# YA-S-Power-Supplies-V1_0.net
KiCad netlist of a schematic drawn in Altium Designer
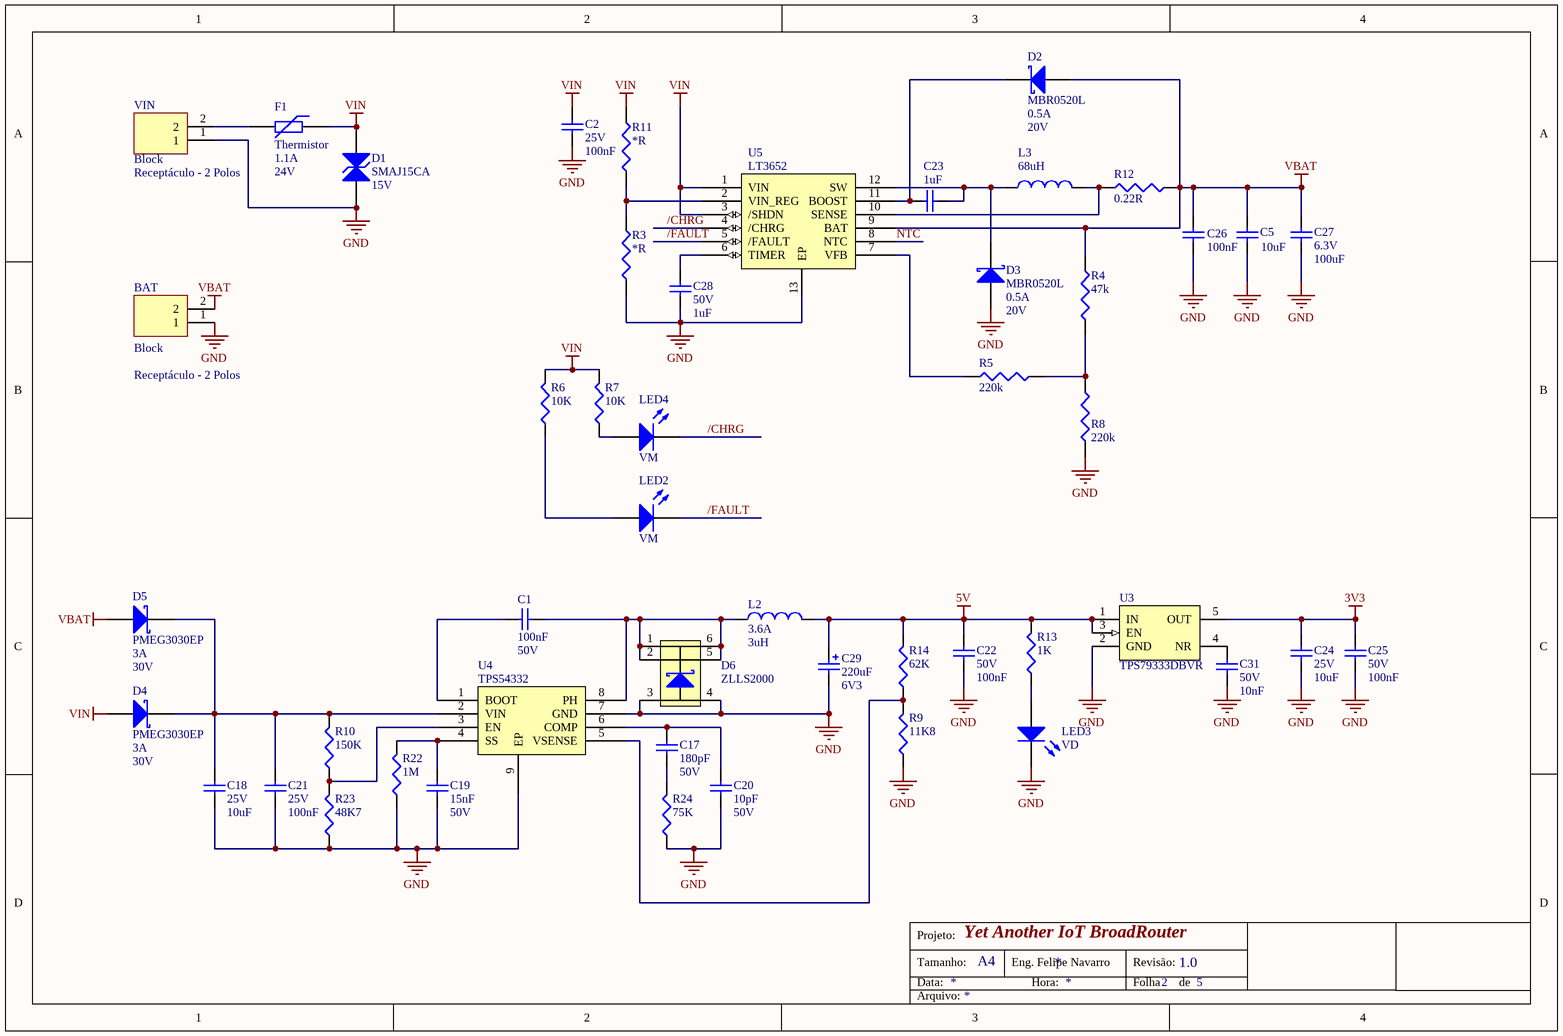
[diagram p0: YA-S-Power-Supplies-V1.0.SchDoc]

(export (version "E")
  (design (tool "Eeschema 10.0.6"))
  (components
    (comp (ref "BAT")
      (value "Block")
      (footprint "CONN SHRD.BL2 RCPT/ V")
      (description "Conector Shrouded Block")
      (fields (field (name "ALTIUM_VALUE") "Receptáculo - 2 Polos"))
      (libsource (lib "NavarroCON") (part "SHRD Block 2P RCPT-V P5.08mm"))
    )
    (comp (ref "C1")
      (value "100nF")
      (footprint "CC0603")
      (description "Capacitor (Semiconductor SIM Model)")
      (fields (field (name "TENSÃO") "50V") (field (name "Comment") "Capacitor Cerâmico"))
      (libsource (lib "NavarroCAP") (part "Cap 100nF 50V 0603 X7R"))
    )
    (comp (ref "C2")
      (value "100nF")
      (footprint "CC0603")
      (description "Capacitor (Semiconductor SIM Model)")
      (fields (field (name "TENSÃO") "25V") (field (name "Comment") "Capacitor Cerâmico"))
      (libsource (lib "NavarroCAP") (part "Cap 100nF 25V 0603 X7R"))
    )
    (comp (ref "C5")
      (value "10uF")
      (footprint "CC0805")
      (description "Capacitor (Semiconductor SIM Model)")
      (fields (field (name "Comment") "Capacitor Cerâmico"))
      (libsource (lib "NavarroCAP") (part "Cap 10uF 50V 1206 X5R"))
    )
    (comp (ref "C17")
      (value "180pF")
      (footprint "CC0603")
      (description "Capacitor (Semiconductor SIM Model)")
      (fields (field (name "TENSÃO") "50V") (field (name "Comment") "Capacitor Cerâmico"))
      (libsource (lib "NavarroCAP") (part "Cap 180pF 50V 0603 NP0"))
    )
    (comp (ref "C18")
      (value "10uF")
      (footprint "CC0805")
      (description "Capacitor (Semiconductor SIM Model)")
      (fields (field (name "TENSÃO") "25V") (field (name "Comment") "Capacitor Cerâmico"))
      (libsource (lib "NavarroCAP") (part "Cap 10uF 25V 0805 X5R"))
    )
    (comp (ref "C19")
      (value "15nF")
      (footprint "CC0603")
      (description "Capacitor (Semiconductor SIM Model)")
      (fields (field (name "TENSÃO") "50V") (field (name "Comment") "Capacitor Cerâmico"))
      (libsource (lib "NavarroCAP") (part "Cap 15nF 50V 0603 X7R"))
    )
    (comp (ref "C20")
      (value "10pF")
      (footprint "CC0603")
      (description "Capacitor (Semiconductor SIM Model)")
      (fields (field (name "TENSÃO") "50V") (field (name "Comment") "Capacitor Cerâmico"))
      (libsource (lib "NavarroCAP") (part "Cap 10pF 50V 0603 NP0 5%"))
    )
    (comp (ref "C21")
      (value "100nF")
      (footprint "CC0603")
      (description "Capacitor (Semiconductor SIM Model)")
      (fields (field (name "TENSÃO") "25V") (field (name "Comment") "Capacitor Cerâmico"))
      (libsource (lib "NavarroCAP") (part "Cap 100nF 25V 0603 X7R"))
    )
    (comp (ref "C22")
      (value "100nF")
      (footprint "CC0603")
      (description "Capacitor (Semiconductor SIM Model)")
      (fields (field (name "TENSÃO") "50V") (field (name "Comment") "Capacitor Cerâmico"))
      (libsource (lib "NavarroCAP") (part "Cap 100nF 50V 0603 X7R"))
    )
    (comp (ref "C23")
      (value "1uF")
      (footprint "CC0603")
      (description "Capacitor (Semiconductor SIM Model)")
      (fields (field (name "Comment") "Capacitor Cerâmico"))
      (libsource (lib "NavarroCAP") (part "Cap 1uF 50V 0603 X5R"))
    )
    (comp (ref "C24")
      (value "10uF")
      (footprint "CC0805")
      (description "Capacitor (Semiconductor SIM Model)")
      (fields (field (name "TENSÃO") "25V") (field (name "Comment") "Capacitor Cerâmico"))
      (libsource (lib "NavarroCAP") (part "Cap 10uF 25V 0805 X5R"))
    )
    (comp (ref "C25")
      (value "100nF")
      (footprint "CC0603")
      (description "Capacitor (Semiconductor SIM Model)")
      (fields (field (name "TENSÃO") "50V") (field (name "Comment") "Capacitor Cerâmico"))
      (libsource (lib "NavarroCAP") (part "Cap 100nF 50V 0603 X7R"))
    )
    (comp (ref "C26")
      (value "100nF")
      (footprint "CC0603")
      (description "Capacitor (Semiconductor SIM Model)")
      (fields (field (name "Comment") "Capacitor Cerâmico"))
      (libsource (lib "NavarroCAP") (part "Cap 100nF 25V 0603 X7R"))
    )
    (comp (ref "C27")
      (value "100uF")
      (footprint "CC1206")
      (description "Capacitor (Semiconductor SIM Model)")
      (fields (field (name "TENSÃO") "6.3V") (field (name "Comment") "Capacitor Cerâmico"))
      (libsource (lib "NavarroCAP") (part "Cap 100uF 6.3V 1206 X5R"))
    )
    (comp (ref "C28")
      (value "1uF")
      (footprint "CC0603")
      (description "Capacitor (Semiconductor SIM Model)")
      (fields (field (name "TENSÃO") "50V") (field (name "Comment") "Capacitor Cerâmico"))
      (libsource (lib "NavarroCAP") (part "Cap 1uF 50V 0603 X5R"))
    )
    (comp (ref "C29")
      (value "220uF")
      (footprint "CPOL2917")
      (description "Polarized Capacitor")
      (fields (field (name "TENSÃO") "6V3") (field (name "Comment") "Capacitor Tântalo"))
      (libsource (lib "NavarroCAP") (part "PCap 220uF 6V3 2917 LOESR"))
    )
    (comp (ref "C31")
      (value "10nF")
      (footprint "CC0603")
      (description "Capacitor (Semiconductor SIM Model)")
      (fields (field (name "TENSÃO") "50V") (field (name "Comment") "Capacitor Cerâmico"))
      (libsource (lib "NavarroCAP") (part "Cap 10nF 50V 0603 X7R 5%"))
    )
    (comp (ref "D1")
      (value "SMAJ15CA")
      (footprint "SMA BIDIR")
      (description "Transient Voltage Supressor diode")
      (fields (field (name "TENSÃO") "15V"))
      (libsource (lib "NavarroSEMI") (part "TVS 15V 5% SMA BI 400W"))
    )
    (comp (ref "D2")
      (value "MBR0520L")
      (footprint "SOD-123F")
      (description "Schottky Diode")
      (fields (field (name "CORRENTE") "0.5A") (field (name "TENSÃO") "20V"))
      (libsource (lib "NavarroSEMI") (part "DS 20V 0.5A 385mV SOD-123"))
    )
    (comp (ref "D3")
      (value "MBR0520L")
      (footprint "SOD-123F")
      (description "Schottky Diode")
      (fields (field (name "CORRENTE") "0.5A") (field (name "TENSÃO") "20V"))
      (libsource (lib "NavarroSEMI") (part "DS 20V 0.5A 385mV SOD-123"))
    )
    (comp (ref "D4")
      (value "PMEG3030EP")
      (footprint "SOD-128")
      (description "Schottky Diode")
      (fields (field (name "CORRENTE") "3A") (field (name "TENSÃO") "30V"))
      (libsource (lib "NavarroSEMI") (part "DS 30V 3A SOD-128"))
    )
    (comp (ref "D5")
      (value "PMEG3030EP")
      (footprint "SOD-128")
      (description "Schottky Diode")
      (fields (field (name "CORRENTE") "3A") (field (name "TENSÃO") "30V"))
      (libsource (lib "NavarroSEMI") (part "DS 30V 3A SOD-128"))
    )
    (comp (ref "D6")
      (value "ZLLS2000")
      (footprint "SOT-23-6N")
      (description "Power Shottky")
      (libsource (lib "NavarroSEMI") (part "DPS 40V 2.2A SOT-23-6N"))
    )
    (comp (ref "F1")
      (value "Thermistor")
      (footprint "CC1812")
      (description "Varistor (Voltage-Sensitive Resistor)")
      (fields (field (name "CORRENTE") "1.1A") (field (name "TENSÃO") "24V"))
      (libsource (lib "Miscellaneous Devices") (part "Res Varistor"))
    )
    (comp (ref "L2")
      (value "3uH")
      (footprint "NR2424")
      (description "Inductor")
      (fields (field (name "CORRENTE") "3.6A") (field (name "Comment") "Indutor"))
      (libsource (lib "NavarroIND") (part "Ind 3uH 2424 3.6A"))
    )
    (comp (ref "L3")
      (value "68uH")
      (footprint "MURATA 4600")
      (description "Inductor")
      (fields (field (name "Comment") "Indutor"))
      (libsource (lib "NavarroIND") (part "Ind 68uH 1.05A"))
    )
    (comp (ref "LED2")
      (value "VM")
      (footprint "LED 0603")
      (description "LED")
      (libsource (lib "NavarroSEMI") (part "LED"))
    )
    (comp (ref "LED3")
      (value "VD")
      (footprint "LED 0603")
      (description "LED")
      (libsource (lib "NavarroSEMI") (part "LED 0603 VD 2V 75mW"))
    )
    (comp (ref "LED4")
      (value "VM")
      (footprint "LED 0603")
      (description "LED")
      (libsource (lib "NavarroSEMI") (part "LED"))
    )
    (comp (ref "R3")
      (value "*R")
      (footprint "CC0603")
      (description "Resistor")
      (libsource (lib "NavarroRES") (part "Res - $Val $% $Footprint $Pot"))
    )
    (comp (ref "R4")
      (value "47k")
      (footprint "CC0603")
      (description "Resistor")
      (libsource (lib "NavarroRES") (part "Res - $Val $% $Footprint $Pot"))
    )
    (comp (ref "R5")
      (value "220k")
      (footprint "CC0603")
      (description "Resistor")
      (libsource (lib "NavarroRES") (part "Res - $Val $% $Footprint $Pot"))
    )
    (comp (ref "R6")
      (value "10K")
      (footprint "CC0603")
      (description "Resistor")
      (libsource (lib "NavarroRES") (part "Res 10K 1% 0603 1/10W"))
    )
    (comp (ref "R7")
      (value "10K")
      (footprint "CC0603")
      (description "Resistor")
      (libsource (lib "NavarroRES") (part "Res 10K 1% 0603 1/10W"))
    )
    (comp (ref "R8")
      (value "220k")
      (footprint "CC0603")
      (description "Resistor")
      (libsource (lib "NavarroRES") (part "Res - $Val $% $Footprint $Pot"))
    )
    (comp (ref "R9")
      (value "11K8")
      (footprint "CC0603")
      (description "Resistor")
      (libsource (lib "NavarroRES") (part "Res 11K8 1% 0603 1/10W"))
    )
    (comp (ref "R10")
      (value "150K")
      (footprint "CC0603")
      (description "Resistor")
      (libsource (lib "NavarroRES") (part "Res 150K 1% 0603 1/10W"))
    )
    (comp (ref "R11")
      (value "*R")
      (footprint "CC0603")
      (description "Resistor")
      (libsource (lib "NavarroRES") (part "Res - $Val $% $Footprint $Pot"))
    )
    (comp (ref "R12")
      (value "0.22R")
      (footprint "CC1206")
      (description "Resistor")
      (libsource (lib "NavarroRES") (part "Res 0.22R 1% 1206 1/4W"))
    )
    (comp (ref "R13")
      (value "1K")
      (footprint "CC0603")
      (description "Resistor")
      (libsource (lib "NavarroRES") (part "Res 1K 1% 0603 1/10W"))
    )
    (comp (ref "R14")
      (value "62K")
      (footprint "CC0603")
      (description "Resistor")
      (libsource (lib "NavarroRES") (part "Res 62K 1% 0603 1/10W"))
    )
    (comp (ref "R22")
      (value "1M")
      (footprint "CC0603")
      (description "Resistor")
      (libsource (lib "NavarroRES") (part "Res 1M 1% 0603 1/10W"))
    )
    (comp (ref "R23")
      (value "48K7")
      (footprint "CC0603")
      (description "Resistor")
      (libsource (lib "NavarroRES") (part "Res 48K7 1% 0603 1/10W"))
    )
    (comp (ref "R24")
      (value "75K")
      (footprint "CC0603")
      (description "Resistor")
      (libsource (lib "NavarroRES") (part "Res 75K 1% 0603 1/10W"))
    )
    (comp (ref "U3")
      (value "TPS79333DBVR")
      (footprint "SOT-23-5N")
      (description "ULTRALOW-NOISE, HIGH PSRR, FAST RF 200mA LOW-DROPOUT LINEAR  REGULATORS I")
      (libsource (lib "Navarro") (part "TPS79333"))
    )
    (comp (ref "U4")
      (value "TPS54332")
      (footprint "SOIC-8N-EP")
      (description "DC/DC Converter Step-Down 3.5A 28V")
      (libsource (lib "Navarro") (part "TPS54332"))
    )
    (comp (ref "U5")
      (value "LT3652")
      (footprint "MSOP-12N_EP")
      (description "Power Tracking 2A Battery  Charger for Solar Power")
      (libsource (lib "Navarro") (part "LT3652"))
    )
    (comp (ref "VIN")
      (value "Block")
      (footprint "CONN SHRD.BL2 RCPT/ V")
      (description "Conector Shrouded Block")
      (fields (field (name "ALTIUM_VALUE") "Receptáculo - 2 Polos"))
      (libsource (lib "NavarroCON") (part "SHRD Block 2P RCPT-V P5.08mm"))
    )
  )
  (nets
    (net (code "1") (name "/NTC") (class "Default")
      (node (ref "U5") (pin "8") (pinfunction "NTC_8") (pintype "passive"))
    )
    (net (code "2") (name "/{slash}CHRG") (class "Default")
      (node (ref "LED4") (pin "2") (pinfunction "K_2") (pintype "passive"))
      (node (ref "U5") (pin "4") (pinfunction "/CHRG_4") (pintype "bidirectional"))
    )
    (net (code "3") (name "/{slash}FAULT") (class "Default")
      (node (ref "LED2") (pin "2") (pinfunction "K_2") (pintype "passive"))
      (node (ref "U5") (pin "5") (pinfunction "/FAULT_5") (pintype "bidirectional"))
    )
    (net (code "4") (name "3V3") (class "Default")
      (node (ref "C24") (pin "2") (pinfunction "2_2") (pintype "passive"))
      (node (ref "C25") (pin "2") (pinfunction "2_2") (pintype "passive"))
      (node (ref "U3") (pin "5") (pinfunction "OUT_5") (pintype "power_in"))
    )
    (net (code "5") (name "5V") (class "Default")
      (node (ref "C22") (pin "2") (pinfunction "2_2") (pintype "passive"))
      (node (ref "C29") (pin "1") (pinfunction "1_1") (pintype "passive"))
      (node (ref "L2") (pin "2") (pinfunction "2_2") (pintype "passive"))
      (node (ref "R13") (pin "2") (pinfunction "2_2") (pintype "passive"))
      (node (ref "R14") (pin "2") (pinfunction "2_2") (pintype "passive"))
      (node (ref "U3") (pin "1") (pinfunction "IN_1") (pintype "power_in"))
      (node (ref "U3") (pin "3") (pinfunction "EN_3") (pintype "input"))
    )
    (net (code "6") (name "GND") (class "Default")
      (node (ref "BAT") (pin "1") (pinfunction "1_1") (pintype "passive"))
      (node (ref "C18") (pin "1") (pinfunction "1_1") (pintype "passive"))
      (node (ref "C19") (pin "1") (pinfunction "1_1") (pintype "passive"))
      (node (ref "C2") (pin "1") (pinfunction "1_1") (pintype "passive"))
      (node (ref "C20") (pin "1") (pinfunction "1_1") (pintype "passive"))
      (node (ref "C21") (pin "1") (pinfunction "1_1") (pintype "passive"))
      (node (ref "C22") (pin "1") (pinfunction "1_1") (pintype "passive"))
      (node (ref "C24") (pin "1") (pinfunction "1_1") (pintype "passive"))
      (node (ref "C25") (pin "1") (pinfunction "1_1") (pintype "passive"))
      (node (ref "C26") (pin "1") (pinfunction "1_1") (pintype "passive"))
      (node (ref "C27") (pin "1") (pinfunction "1_1") (pintype "passive"))
      (node (ref "C28") (pin "1") (pinfunction "1_1") (pintype "passive"))
      (node (ref "C29") (pin "2") (pinfunction "2_2") (pintype "passive"))
      (node (ref "C31") (pin "1") (pinfunction "1_1") (pintype "passive"))
      (node (ref "C5") (pin "1") (pinfunction "1_1") (pintype "passive"))
      (node (ref "D1") (pin "1") (pinfunction "A_1") (pintype "passive"))
      (node (ref "D3") (pin "1") (pinfunction "A_1") (pintype "passive"))
      (node (ref "D6") (pin "3") (pinfunction "A_3") (pintype "passive"))
      (node (ref "D6") (pin "4") (pinfunction "A_4") (pintype "passive"))
      (node (ref "LED3") (pin "2") (pinfunction "K_2") (pintype "passive"))
      (node (ref "R22") (pin "1") (pinfunction "1_1") (pintype "passive"))
      (node (ref "R23") (pin "1") (pinfunction "1_1") (pintype "passive"))
      (node (ref "R24") (pin "1") (pinfunction "1_1") (pintype "passive"))
      (node (ref "R3") (pin "1") (pinfunction "1_1") (pintype "passive"))
      (node (ref "R8") (pin "1") (pinfunction "1_1") (pintype "passive"))
      (node (ref "R9") (pin "1") (pinfunction "1_1") (pintype "passive"))
      (node (ref "U3") (pin "2") (pinfunction "GND_2") (pintype "power_in"))
      (node (ref "U4") (pin "7") (pinfunction "GND_7") (pintype "passive"))
      (node (ref "U4") (pin "9") (pinfunction "EP_9") (pintype "passive"))
      (node (ref "U5") (pin "13") (pinfunction "EP_13") (pintype "passive"))
      (node (ref "VIN") (pin "1") (pinfunction "1_1") (pintype "passive"))
    )
    (net (code "7") (name "Net-(C17-Pad1)") (class "Default")
      (node (ref "C17") (pin "1") (pinfunction "1_1") (pintype "passive"))
      (node (ref "R24") (pin "2") (pinfunction "2_2") (pintype "passive"))
    )
    (net (code "8") (name "Net-(D2-K)") (class "Default")
      (node (ref "C23") (pin "1") (pinfunction "1_1") (pintype "passive"))
      (node (ref "D2") (pin "2") (pinfunction "K_2") (pintype "passive"))
      (node (ref "U5") (pin "11") (pinfunction "BOOST_11") (pintype "passive"))
    )
    (net (code "9") (name "Net-(D3-K)") (class "Default")
      (node (ref "C23") (pin "2") (pinfunction "2_2") (pintype "passive"))
      (node (ref "D3") (pin "2") (pinfunction "K_2") (pintype "passive"))
      (node (ref "L3") (pin "1") (pinfunction "1_1") (pintype "passive"))
      (node (ref "U5") (pin "12") (pinfunction "SW_12") (pintype "passive"))
    )
    (net (code "10") (name "Net-(D4-K)") (class "Default")
      (node (ref "C18") (pin "2") (pinfunction "2_2") (pintype "passive"))
      (node (ref "C21") (pin "2") (pinfunction "2_2") (pintype "passive"))
      (node (ref "D4") (pin "2") (pinfunction "K_2") (pintype "passive"))
      (node (ref "D5") (pin "2") (pinfunction "K_2") (pintype "passive"))
      (node (ref "R10") (pin "2") (pinfunction "2_2") (pintype "passive"))
      (node (ref "U4") (pin "2") (pinfunction "VIN_2") (pintype "passive"))
    )
    (net (code "11") (name "Net-(F1-Pad2)") (class "Default")
      (node (ref "F1") (pin "2") (pinfunction "2_2") (pintype "passive"))
      (node (ref "VIN") (pin "2") (pinfunction "2_2") (pintype "passive"))
    )
    (net (code "12") (name "Net-(LED2-A)") (class "Default")
      (node (ref "LED2") (pin "1") (pinfunction "A_1") (pintype "passive"))
      (node (ref "R6") (pin "1") (pinfunction "1_1") (pintype "passive"))
    )
    (net (code "13") (name "Net-(LED3-A)") (class "Default")
      (node (ref "LED3") (pin "1") (pinfunction "A_1") (pintype "passive"))
      (node (ref "R13") (pin "1") (pinfunction "1_1") (pintype "passive"))
    )
    (net (code "14") (name "Net-(LED4-A)") (class "Default")
      (node (ref "LED4") (pin "1") (pinfunction "A_1") (pintype "passive"))
      (node (ref "R7") (pin "1") (pinfunction "1_1") (pintype "passive"))
    )
    (net (code "15") (name "Net-(R4-Pad1)") (class "Default")
      (node (ref "R4") (pin "1") (pinfunction "1_1") (pintype "passive"))
      (node (ref "R5") (pin "1") (pinfunction "1_1") (pintype "passive"))
      (node (ref "R8") (pin "2") (pinfunction "2_2") (pintype "passive"))
    )
    (net (code "16") (name "Net-(U3-NR)") (class "Default")
      (node (ref "C31") (pin "2") (pinfunction "2_2") (pintype "passive"))
      (node (ref "U3") (pin "4") (pinfunction "NR_4") (pintype "passive"))
    )
    (net (code "17") (name "Net-(U4-BOOT)") (class "Default")
      (node (ref "C1") (pin "2") (pinfunction "2_2") (pintype "passive"))
      (node (ref "U4") (pin "1") (pinfunction "BOOT_1") (pintype "passive"))
    )
    (net (code "18") (name "Net-(U4-COMP)") (class "Default")
      (node (ref "C17") (pin "2") (pinfunction "2_2") (pintype "passive"))
      (node (ref "C20") (pin "2") (pinfunction "2_2") (pintype "passive"))
      (node (ref "U4") (pin "6") (pinfunction "COMP_6") (pintype "passive"))
    )
    (net (code "19") (name "Net-(U4-EN)") (class "Default")
      (node (ref "R10") (pin "1") (pinfunction "1_1") (pintype "passive"))
      (node (ref "R23") (pin "2") (pinfunction "2_2") (pintype "passive"))
      (node (ref "U4") (pin "3") (pinfunction "EN_3") (pintype "passive"))
    )
    (net (code "20") (name "Net-(U4-PH)") (class "Default")
      (node (ref "C1") (pin "1") (pinfunction "1_1") (pintype "passive"))
      (node (ref "D6") (pin "1") (pinfunction "C_1") (pintype "passive"))
      (node (ref "D6") (pin "2") (pinfunction "C_2") (pintype "passive"))
      (node (ref "D6") (pin "5") (pinfunction "C_5") (pintype "passive"))
      (node (ref "D6") (pin "6") (pinfunction "C_6") (pintype "passive"))
      (node (ref "L2") (pin "1") (pinfunction "1_1") (pintype "passive"))
      (node (ref "U4") (pin "8") (pinfunction "PH_8") (pintype "passive"))
    )
    (net (code "21") (name "Net-(U4-SS)") (class "Default")
      (node (ref "C19") (pin "2") (pinfunction "2_2") (pintype "passive"))
      (node (ref "R22") (pin "2") (pinfunction "2_2") (pintype "passive"))
      (node (ref "U4") (pin "4") (pinfunction "SS_4") (pintype "passive"))
    )
    (net (code "22") (name "Net-(U4-VSENSE)") (class "Default")
      (node (ref "R14") (pin "1") (pinfunction "1_1") (pintype "passive"))
      (node (ref "R9") (pin "2") (pinfunction "2_2") (pintype "passive"))
      (node (ref "U4") (pin "5") (pinfunction "VSENSE_5") (pintype "passive"))
    )
    (net (code "23") (name "Net-(U5-SENSE)") (class "Default")
      (node (ref "L3") (pin "2") (pinfunction "2_2") (pintype "passive"))
      (node (ref "R12") (pin "1") (pinfunction "1_1") (pintype "passive"))
      (node (ref "U5") (pin "10") (pinfunction "SENSE_10") (pintype "passive"))
    )
    (net (code "24") (name "Net-(U5-TIMER)") (class "Default")
      (node (ref "C28") (pin "2") (pinfunction "2_2") (pintype "passive"))
      (node (ref "U5") (pin "6") (pinfunction "TIMER_6") (pintype "bidirectional"))
    )
    (net (code "25") (name "Net-(U5-VFB)") (class "Default")
      (node (ref "R5") (pin "2") (pinfunction "2_2") (pintype "passive"))
      (node (ref "U5") (pin "7") (pinfunction "VFB_7") (pintype "passive"))
    )
    (net (code "26") (name "Net-(U5-VIN_REG)") (class "Default")
      (node (ref "R11") (pin "1") (pinfunction "1_1") (pintype "passive"))
      (node (ref "R3") (pin "2") (pinfunction "2_2") (pintype "passive"))
      (node (ref "U5") (pin "2") (pinfunction "VIN_REG_2") (pintype "power_in"))
    )
    (net (code "27") (name "VBAT") (class "Default")
      (node (ref "BAT") (pin "2") (pinfunction "2_2") (pintype "passive"))
      (node (ref "C26") (pin "2") (pinfunction "2_2") (pintype "passive"))
      (node (ref "C27") (pin "2") (pinfunction "2_2") (pintype "passive"))
      (node (ref "C5") (pin "2") (pinfunction "2_2") (pintype "passive"))
      (node (ref "D2") (pin "1") (pinfunction "A_1") (pintype "passive"))
      (node (ref "D5") (pin "1") (pinfunction "A_1") (pintype "passive"))
      (node (ref "R12") (pin "2") (pinfunction "2_2") (pintype "passive"))
      (node (ref "R4") (pin "2") (pinfunction "2_2") (pintype "passive"))
      (node (ref "U5") (pin "9") (pinfunction "BAT_9") (pintype "power_in"))
    )
    (net (code "28") (name "VIN") (class "Default")
      (node (ref "C2") (pin "2") (pinfunction "2_2") (pintype "passive"))
      (node (ref "D1") (pin "2") (pinfunction "K_2") (pintype "passive"))
      (node (ref "D4") (pin "1") (pinfunction "A_1") (pintype "passive"))
      (node (ref "F1") (pin "1") (pinfunction "1_1") (pintype "passive"))
      (node (ref "R11") (pin "2") (pinfunction "2_2") (pintype "passive"))
      (node (ref "R6") (pin "2") (pinfunction "2_2") (pintype "passive"))
      (node (ref "R7") (pin "2") (pinfunction "2_2") (pintype "passive"))
      (node (ref "U5") (pin "1") (pinfunction "VIN_1") (pintype "power_in"))
      (node (ref "U5") (pin "3") (pinfunction "/SHDN_3") (pintype "bidirectional"))
    )
  )
)
